# mcu.net
KiCad netlist of a schematic drawn in EAGLE
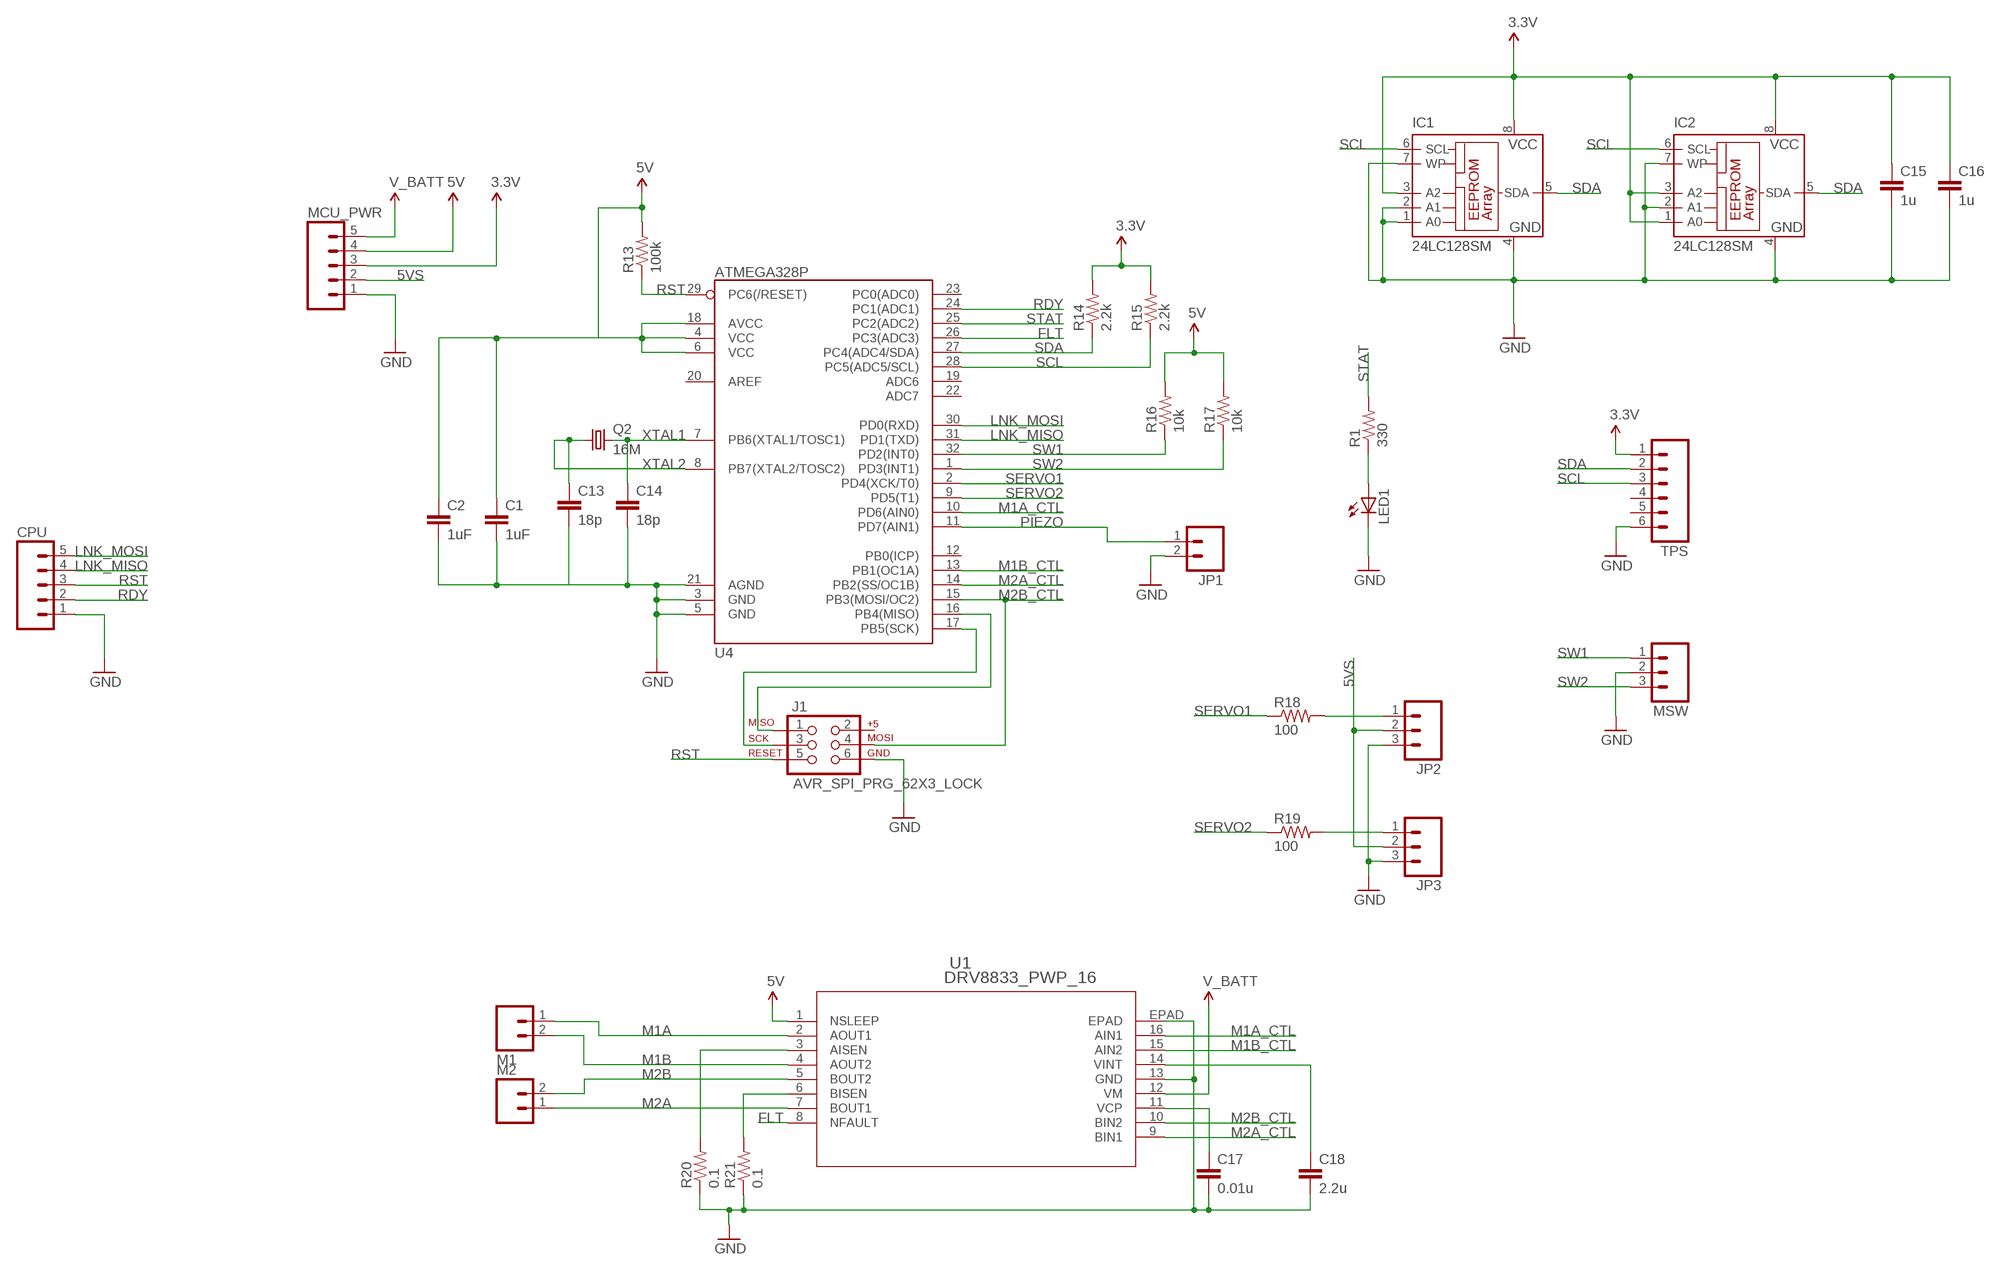
[diagram p0: schematic, sheet 1]

(export (version "E")
  (design (tool "Eeschema 10.0.6"))
  (components
    (comp (ref "C1")
      (value "1uF")
      (footprint "eagle-import:0805")
      (libsource (lib "eagle-import") (part "1UF-25V-10%(0805)"))
    )
    (comp (ref "C2")
      (value "1uF")
      (footprint "eagle-import:0805")
      (libsource (lib "eagle-import") (part "1UF-25V-10%(0805)"))
    )
    (comp (ref "C13")
      (value "18p")
      (footprint "eagle-import:0805")
      (libsource (lib "eagle-import") (part "CAP0805"))
    )
    (comp (ref "C14")
      (value "18p")
      (footprint "eagle-import:0805")
      (libsource (lib "eagle-import") (part "CAP0805"))
    )
    (comp (ref "C15")
      (value "1u")
      (footprint "eagle-import:0805")
      (libsource (lib "eagle-import") (part "CAP0805"))
    )
    (comp (ref "C16")
      (value "1u")
      (footprint "eagle-import:0805")
      (libsource (lib "eagle-import") (part "CAP0805"))
    )
    (comp (ref "C17")
      (value "0.01u")
      (footprint "eagle-import:0805")
      (libsource (lib "eagle-import") (part "CAP0805"))
    )
    (comp (ref "C18")
      (value "2.2u")
      (footprint "eagle-import:0805")
      (libsource (lib "eagle-import") (part "CAP0805"))
    )
    (comp (ref "CPU")
      (value "M05PTH_LONGPADS")
      (footprint "eagle-import:1X05_LONGPADS")
      (libsource (lib "eagle-import") (part "M05PTH_LONGPADS"))
    )
    (comp (ref "IC1")
      (value "24LC128SM")
      (footprint "eagle-import:SO-08M")
      (fields (field (name "MF") "MICROCHIP") (field (name "MPN") "24LC128-I/SM"))
      (libsource (lib "eagle-import") (part "24SMLC128"))
    )
    (comp (ref "IC2")
      (value "24LC128SM")
      (footprint "eagle-import:SO-08M")
      (fields (field (name "MF") "MICROCHIP") (field (name "MPN") "24LC128-I/SM"))
      (libsource (lib "eagle-import") (part "24SMLC128"))
    )
    (comp (ref "J1")
      (value "AVR_SPI_PRG_62X3_LOCK")
      (footprint "eagle-import:2X3_LOCK")
      (libsource (lib "eagle-import") (part "AVR_SPI_PRG_62X3_LOCK"))
    )
    (comp (ref "JP1")
      (value "M02PTH3")
      (footprint "eagle-import:1X02_LONGPADS")
      (libsource (lib "eagle-import") (part "M02PTH3"))
    )
    (comp (ref "JP2")
      (value "M03LOCK_LONGPADS")
      (footprint "eagle-import:1X03_LOCK_LONGPADS")
      (libsource (lib "eagle-import") (part "M03LOCK_LONGPADS"))
    )
    (comp (ref "JP3")
      (value "M03LOCK_LONGPADS")
      (footprint "eagle-import:1X03_LOCK_LONGPADS")
      (libsource (lib "eagle-import") (part "M03LOCK_LONGPADS"))
    )
    (comp (ref "LED1")
      (value "LED1206")
      (footprint "eagle-import:LED-1206")
      (libsource (lib "eagle-import") (part "LED1206"))
    )
    (comp (ref "M1")
      (value "M02PTH3")
      (footprint "eagle-import:1X02_LONGPADS")
      (libsource (lib "eagle-import") (part "M02PTH3"))
    )
    (comp (ref "M2")
      (value "M02PTH3")
      (footprint "eagle-import:1X02_LONGPADS")
      (libsource (lib "eagle-import") (part "M02PTH3"))
    )
    (comp (ref "MCU_PWR")
      (value "M05PTH")
      (footprint "eagle-import:1X05")
      (libsource (lib "eagle-import") (part "M05PTH"))
    )
    (comp (ref "MSW")
      (value "M03LONGPADS")
      (footprint "eagle-import:1X03_LONGPADS")
      (libsource (lib "eagle-import") (part "M03LONGPADS"))
    )
    (comp (ref "Q2")
      (value "16M")
      (footprint "eagle-import:HC49UP")
      (libsource (lib "eagle-import") (part "CRYSTALHC49UP"))
    )
    (comp (ref "R1")
      (value "330")
      (footprint "eagle-import:0805")
      (libsource (lib "eagle-import") (part "RESISTOR0805-RES"))
    )
    (comp (ref "R13")
      (value "100k")
      (footprint "eagle-import:0805")
      (libsource (lib "eagle-import") (part "RESISTOR0805-RES"))
    )
    (comp (ref "R14")
      (value "2.2k")
      (footprint "eagle-import:0805")
      (libsource (lib "eagle-import") (part "RESISTOR0805-RES"))
    )
    (comp (ref "R15")
      (value "2.2k")
      (footprint "eagle-import:0805")
      (libsource (lib "eagle-import") (part "RESISTOR0805-RES"))
    )
    (comp (ref "R16")
      (value "10k")
      (footprint "eagle-import:0805")
      (libsource (lib "eagle-import") (part "RESISTOR0805-RES"))
    )
    (comp (ref "R17")
      (value "10k")
      (footprint "eagle-import:0805")
      (libsource (lib "eagle-import") (part "RESISTOR0805-RES"))
    )
    (comp (ref "R18")
      (value "100")
      (footprint "eagle-import:0805")
      (libsource (lib "eagle-import") (part "RESISTOR0805-RES"))
    )
    (comp (ref "R19")
      (value "100")
      (footprint "eagle-import:0805")
      (libsource (lib "eagle-import") (part "RESISTOR0805-RES"))
    )
    (comp (ref "R20")
      (value "0.1")
      (footprint "eagle-import:1206")
      (libsource (lib "eagle-import") (part "RESISTOR1206"))
    )
    (comp (ref "R21")
      (value "0.1")
      (footprint "eagle-import:1206")
      (libsource (lib "eagle-import") (part "RESISTOR1206"))
    )
    (comp (ref "TPS")
      (value "M06LOCK")
      (footprint "eagle-import:1X06_LOCK")
      (libsource (lib "eagle-import") (part "M06LOCK"))
    )
    (comp (ref "U1")
      (value "DRV8833_PWP_16")
      (footprint "eagle-import:PWP16_2P31X2P46")
      (fields
        (field (name "GENERIC_PART_NUMBER") "DRV8833")
        (field (name "MANUFACTURER") "Texas Instruments")
        (field (name "MANUFACTURER_PART_NUMBER") "drv8833_pwp_16")
      )
      (libsource (lib "eagle-import") (part "DRV8833_PWP_16"))
    )
    (comp (ref "U4")
      (value "ATMEGA328P")
      (footprint "eagle-import:TQFP32-08")
      (libsource (lib "eagle-import") (part "ATMEGA328_SMT"))
    )
  )
  (nets
    (net (code "1") (name "/5VS") (class "Default")
      (node (ref "JP2") (pin "2") (pinfunction "2_2") (pintype "passive"))
      (node (ref "JP3") (pin "2") (pinfunction "2_2") (pintype "passive"))
      (node (ref "MCU_PWR") (pin "2") (pinfunction "2_2") (pintype "passive"))
    )
    (net (code "2") (name "/FLT") (class "Default")
      (node (ref "U1") (pin "8") (pinfunction "NFAULT_8") (pintype "output"))
      (node (ref "U4") (pin "26") (pinfunction "PC3(ADC3)_26") (pintype "bidirectional"))
    )
    (net (code "3") (name "/LNK_MISO") (class "Default")
      (node (ref "CPU") (pin "4") (pinfunction "4_4") (pintype "passive"))
      (node (ref "U4") (pin "31") (pinfunction "PD1(TXD)_31") (pintype "bidirectional"))
    )
    (net (code "4") (name "/LNK_MOSI") (class "Default")
      (node (ref "CPU") (pin "5") (pinfunction "5_5") (pintype "passive"))
      (node (ref "U4") (pin "30") (pinfunction "PD0(RXD)_30") (pintype "bidirectional"))
    )
    (net (code "5") (name "/M1A") (class "Default")
      (node (ref "M1") (pin "1") (pinfunction "1_1") (pintype "passive"))
      (node (ref "U1") (pin "2") (pinfunction "AOUT1_2") (pintype "output"))
    )
    (net (code "6") (name "/M1A_CTL") (class "Default")
      (node (ref "U1") (pin "16") (pinfunction "AIN1_16") (pintype "input"))
      (node (ref "U4") (pin "10") (pinfunction "PD6(AIN0)_10") (pintype "bidirectional"))
    )
    (net (code "7") (name "/M1B") (class "Default")
      (node (ref "M1") (pin "2") (pinfunction "2_2") (pintype "passive"))
      (node (ref "U1") (pin "4") (pinfunction "AOUT2_4") (pintype "output"))
    )
    (net (code "8") (name "/M1B_CTL") (class "Default")
      (node (ref "U1") (pin "15") (pinfunction "AIN2_15") (pintype "input"))
      (node (ref "U4") (pin "13") (pinfunction "PB1(OC1A)_13") (pintype "bidirectional"))
    )
    (net (code "9") (name "/M2A") (class "Default")
      (node (ref "M2") (pin "1") (pinfunction "1_1") (pintype "passive"))
      (node (ref "U1") (pin "7") (pinfunction "BOUT1_7") (pintype "output"))
    )
    (net (code "10") (name "/M2A_CTL") (class "Default")
      (node (ref "U1") (pin "9") (pinfunction "BIN1_9") (pintype "input"))
      (node (ref "U4") (pin "14") (pinfunction "PB2(SS/OC1B)_14") (pintype "bidirectional"))
    )
    (net (code "11") (name "/M2B") (class "Default")
      (node (ref "M2") (pin "2") (pinfunction "2_2") (pintype "passive"))
      (node (ref "U1") (pin "5") (pinfunction "BOUT2_5") (pintype "output"))
    )
    (net (code "12") (name "/M2B_CTL") (class "Default")
      (node (ref "J1") (pin "4") (pinfunction "4_4") (pintype "passive"))
      (node (ref "U1") (pin "10") (pinfunction "BIN2_10") (pintype "input"))
      (node (ref "U4") (pin "15") (pinfunction "PB3(MOSI/OC2)_15") (pintype "bidirectional"))
    )
    (net (code "13") (name "/PIEZO") (class "Default")
      (node (ref "JP1") (pin "1") (pinfunction "1_1") (pintype "passive"))
      (node (ref "U4") (pin "11") (pinfunction "PD7(AIN1)_11") (pintype "bidirectional"))
    )
    (net (code "14") (name "/RDY") (class "Default")
      (node (ref "CPU") (pin "2") (pinfunction "2_2") (pintype "passive"))
      (node (ref "U4") (pin "24") (pinfunction "PC1(ADC1)_24") (pintype "bidirectional"))
    )
    (net (code "15") (name "/RST") (class "Default")
      (node (ref "CPU") (pin "3") (pinfunction "3_3") (pintype "passive"))
      (node (ref "J1") (pin "5") (pinfunction "5_5") (pintype "passive"))
      (node (ref "R13") (pin "1") (pinfunction "1_1") (pintype "passive"))
      (node (ref "U4") (pin "29") (pinfunction "PC6(/RESET)_29") (pintype "bidirectional"))
    )
    (net (code "16") (name "/SCL") (class "Default")
      (node (ref "IC1") (pin "6") (pinfunction "SCL_6") (pintype "input"))
      (node (ref "IC2") (pin "6") (pinfunction "SCL_6") (pintype "input"))
      (node (ref "R15") (pin "1") (pinfunction "1_1") (pintype "passive"))
      (node (ref "TPS") (pin "3") (pinfunction "3_3") (pintype "passive"))
      (node (ref "U4") (pin "28") (pinfunction "PC5(ADC5/SCL)_28") (pintype "bidirectional"))
    )
    (net (code "17") (name "/SDA") (class "Default")
      (node (ref "IC1") (pin "5") (pinfunction "SDA_5") (pintype "bidirectional"))
      (node (ref "IC2") (pin "5") (pinfunction "SDA_5") (pintype "bidirectional"))
      (node (ref "R14") (pin "1") (pinfunction "1_1") (pintype "passive"))
      (node (ref "TPS") (pin "2") (pinfunction "2_2") (pintype "passive"))
      (node (ref "U4") (pin "27") (pinfunction "PC4(ADC4/SDA)_27") (pintype "bidirectional"))
    )
    (net (code "18") (name "/SERVO1") (class "Default")
      (node (ref "R18") (pin "1") (pinfunction "1_1") (pintype "passive"))
      (node (ref "U4") (pin "2") (pinfunction "PD4(XCK/T0)_2") (pintype "bidirectional"))
    )
    (net (code "19") (name "/SERVO2") (class "Default")
      (node (ref "R19") (pin "1") (pinfunction "1_1") (pintype "passive"))
      (node (ref "U4") (pin "9") (pinfunction "PD5(T1)_9") (pintype "bidirectional"))
    )
    (net (code "20") (name "/STAT") (class "Default")
      (node (ref "R1") (pin "2") (pinfunction "2_2") (pintype "passive"))
      (node (ref "U4") (pin "25") (pinfunction "PC2(ADC2)_25") (pintype "bidirectional"))
    )
    (net (code "21") (name "/SW1") (class "Default")
      (node (ref "MSW") (pin "1") (pinfunction "1_1") (pintype "passive"))
      (node (ref "R16") (pin "1") (pinfunction "1_1") (pintype "passive"))
      (node (ref "U4") (pin "32") (pinfunction "PD2(INT0)_32") (pintype "bidirectional"))
    )
    (net (code "22") (name "/SW2") (class "Default")
      (node (ref "MSW") (pin "3") (pinfunction "3_3") (pintype "passive"))
      (node (ref "R17") (pin "1") (pinfunction "1_1") (pintype "passive"))
      (node (ref "U4") (pin "1") (pinfunction "PD3(INT1)_1") (pintype "bidirectional"))
    )
    (net (code "23") (name "/XTAL1") (class "Default")
      (node (ref "C14") (pin "1") (pinfunction "1_1") (pintype "passive"))
      (node (ref "Q2") (pin "2") (pinfunction "2_2") (pintype "passive"))
      (node (ref "U4") (pin "7") (pinfunction "PB6(XTAL1/TOSC1)_7") (pintype "bidirectional"))
    )
    (net (code "24") (name "/XTAL2") (class "Default")
      (node (ref "C13") (pin "1") (pinfunction "1_1") (pintype "passive"))
      (node (ref "Q2") (pin "1") (pinfunction "1_1") (pintype "passive"))
      (node (ref "U4") (pin "8") (pinfunction "PB7(XTAL2/TOSC2)_8") (pintype "bidirectional"))
    )
    (net (code "25") (name "3.3V") (class "Default")
      (node (ref "C15") (pin "1") (pinfunction "1_1") (pintype "passive"))
      (node (ref "C16") (pin "1") (pinfunction "1_1") (pintype "passive"))
      (node (ref "IC1") (pin "3") (pinfunction "A2_3") (pintype "input"))
      (node (ref "IC1") (pin "8") (pinfunction "VCC_8") (pintype "power_in"))
      (node (ref "IC2") (pin "1") (pinfunction "A0_1") (pintype "input"))
      (node (ref "IC2") (pin "3") (pinfunction "A2_3") (pintype "input"))
      (node (ref "IC2") (pin "8") (pinfunction "VCC_8") (pintype "power_in"))
      (node (ref "MCU_PWR") (pin "3") (pinfunction "3_3") (pintype "passive"))
      (node (ref "R14") (pin "2") (pinfunction "2_2") (pintype "passive"))
      (node (ref "R15") (pin "2") (pinfunction "2_2") (pintype "passive"))
      (node (ref "TPS") (pin "1") (pinfunction "1_1") (pintype "passive"))
    )
    (net (code "26") (name "5V") (class "Default")
      (node (ref "C1") (pin "1") (pinfunction "1_1") (pintype "passive"))
      (node (ref "C2") (pin "1") (pinfunction "1_1") (pintype "passive"))
      (node (ref "MCU_PWR") (pin "4") (pinfunction "4_4") (pintype "passive"))
      (node (ref "R13") (pin "2") (pinfunction "2_2") (pintype "passive"))
      (node (ref "R16") (pin "2") (pinfunction "2_2") (pintype "passive"))
      (node (ref "R17") (pin "2") (pinfunction "2_2") (pintype "passive"))
      (node (ref "U1") (pin "1") (pinfunction "NSLEEP_1") (pintype "input"))
      (node (ref "U4") (pin "18") (pinfunction "AVCC_18") (pintype "bidirectional"))
      (node (ref "U4") (pin "4") (pinfunction "VCC_4") (pintype "bidirectional"))
      (node (ref "U4") (pin "6") (pinfunction "VCC_6") (pintype "bidirectional"))
    )
    (net (code "27") (name "GND") (class "Default")
      (node (ref "C1") (pin "2") (pinfunction "2_2") (pintype "passive"))
      (node (ref "C13") (pin "2") (pinfunction "2_2") (pintype "passive"))
      (node (ref "C14") (pin "2") (pinfunction "2_2") (pintype "passive"))
      (node (ref "C15") (pin "2") (pinfunction "2_2") (pintype "passive"))
      (node (ref "C16") (pin "2") (pinfunction "2_2") (pintype "passive"))
      (node (ref "C17") (pin "2") (pinfunction "2_2") (pintype "passive"))
      (node (ref "C18") (pin "2") (pinfunction "2_2") (pintype "passive"))
      (node (ref "C2") (pin "2") (pinfunction "2_2") (pintype "passive"))
      (node (ref "CPU") (pin "1") (pinfunction "1_1") (pintype "passive"))
      (node (ref "IC1") (pin "1") (pinfunction "A0_1") (pintype "input"))
      (node (ref "IC1") (pin "2") (pinfunction "A1_2") (pintype "input"))
      (node (ref "IC1") (pin "4") (pinfunction "GND_4") (pintype "power_in"))
      (node (ref "IC1") (pin "7") (pinfunction "WP_7") (pintype "input"))
      (node (ref "IC2") (pin "2") (pinfunction "A1_2") (pintype "input"))
      (node (ref "IC2") (pin "4") (pinfunction "GND_4") (pintype "power_in"))
      (node (ref "IC2") (pin "7") (pinfunction "WP_7") (pintype "input"))
      (node (ref "J1") (pin "6") (pinfunction "6_6") (pintype "passive"))
      (node (ref "JP1") (pin "2") (pinfunction "2_2") (pintype "passive"))
      (node (ref "JP2") (pin "3") (pinfunction "3_3") (pintype "passive"))
      (node (ref "JP3") (pin "3") (pinfunction "3_3") (pintype "passive"))
      (node (ref "LED1") (pin "C") (pinfunction "C_C") (pintype "passive"))
      (node (ref "MCU_PWR") (pin "1") (pinfunction "1_1") (pintype "passive"))
      (node (ref "MSW") (pin "2") (pinfunction "2_2") (pintype "passive"))
      (node (ref "R20") (pin "1") (pinfunction "1_1") (pintype "passive"))
      (node (ref "R21") (pin "1") (pinfunction "1_1") (pintype "passive"))
      (node (ref "TPS") (pin "6") (pinfunction "6_6") (pintype "passive"))
      (node (ref "U1") (pin "13") (pinfunction "GND_13") (pintype "power_in"))
      (node (ref "U1") (pin "EPAD") (pinfunction "EPAD_EPAD") (pintype "passive"))
      (node (ref "U4") (pin "21") (pinfunction "AGND_21") (pintype "bidirectional"))
      (node (ref "U4") (pin "3") (pinfunction "GND_3") (pintype "bidirectional"))
      (node (ref "U4") (pin "5") (pinfunction "GND_5") (pintype "bidirectional"))
    )
    (net (code "28") (name "Net-(JP2-Pad1)") (class "Default")
      (node (ref "JP2") (pin "1") (pinfunction "1_1") (pintype "passive"))
      (node (ref "R18") (pin "2") (pinfunction "2_2") (pintype "passive"))
    )
    (net (code "29") (name "Net-(JP3-Pad1)") (class "Default")
      (node (ref "JP3") (pin "1") (pinfunction "1_1") (pintype "passive"))
      (node (ref "R19") (pin "2") (pinfunction "2_2") (pintype "passive"))
    )
    (net (code "30") (name "Net-(LED1-PadA)") (class "Default")
      (node (ref "LED1") (pin "A") (pinfunction "A_A") (pintype "passive"))
      (node (ref "R1") (pin "1") (pinfunction "1_1") (pintype "passive"))
    )
    (net (code "31") (name "Net-(U1-AISEN)") (class "Default")
      (node (ref "R20") (pin "2") (pinfunction "2_2") (pintype "passive"))
      (node (ref "U1") (pin "3") (pinfunction "AISEN_3") (pintype "bidirectional"))
    )
    (net (code "32") (name "Net-(U1-BISEN)") (class "Default")
      (node (ref "R21") (pin "2") (pinfunction "2_2") (pintype "passive"))
      (node (ref "U1") (pin "6") (pinfunction "BISEN_6") (pintype "bidirectional"))
    )
    (net (code "33") (name "Net-(U1-VCP)") (class "Default")
      (node (ref "C17") (pin "1") (pinfunction "1_1") (pintype "passive"))
      (node (ref "U1") (pin "11") (pinfunction "VCP_11") (pintype "bidirectional"))
    )
    (net (code "34") (name "Net-(U1-VINT)") (class "Default")
      (node (ref "C18") (pin "1") (pinfunction "1_1") (pintype "passive"))
      (node (ref "U1") (pin "14") (pinfunction "VINT_14") (pintype "power_in"))
    )
    (net (code "35") (name "Net-(U4-PB4(MISO))") (class "Default")
      (node (ref "J1") (pin "1") (pinfunction "1_1") (pintype "passive"))
      (node (ref "U4") (pin "16") (pinfunction "PB4(MISO)_16") (pintype "bidirectional"))
    )
    (net (code "36") (name "Net-(U4-PB5(SCK))") (class "Default")
      (node (ref "J1") (pin "3") (pinfunction "3_3") (pintype "passive"))
      (node (ref "U4") (pin "17") (pinfunction "PB5(SCK)_17") (pintype "bidirectional"))
    )
    (net (code "37") (name "V_BATT") (class "Default")
      (node (ref "MCU_PWR") (pin "5") (pinfunction "5_5") (pintype "passive"))
      (node (ref "U1") (pin "12") (pinfunction "VM_12") (pintype "power_in"))
    )
    (net (code "38") (name "unconnected-(J1-Pad2)") (class "Default")
      (node (ref "J1") (pin "2") (pinfunction "2_2") (pintype "passive"))
    )
    (net (code "39") (name "unconnected-(TPS-Pad4)") (class "Default")
      (node (ref "TPS") (pin "4") (pinfunction "4_4") (pintype "passive"))
    )
    (net (code "40") (name "unconnected-(TPS-Pad5)") (class "Default")
      (node (ref "TPS") (pin "5") (pinfunction "5_5") (pintype "passive"))
    )
    (net (code "41") (name "unconnected-(U4-ADC6-Pad19)") (class "Default")
      (node (ref "U4") (pin "19") (pinfunction "ADC6_19") (pintype "bidirectional"))
    )
    (net (code "42") (name "unconnected-(U4-ADC7-Pad22)") (class "Default")
      (node (ref "U4") (pin "22") (pinfunction "ADC7_22") (pintype "bidirectional"))
    )
    (net (code "43") (name "unconnected-(U4-AREF-Pad20)") (class "Default")
      (node (ref "U4") (pin "20") (pinfunction "AREF_20") (pintype "bidirectional"))
    )
    (net (code "44") (name "unconnected-(U4-PB0(ICP)-Pad12)") (class "Default")
      (node (ref "U4") (pin "12") (pinfunction "PB0(ICP)_12") (pintype "bidirectional"))
    )
    (net (code "45") (name "unconnected-(U4-PC0(ADC0)-Pad23)") (class "Default")
      (node (ref "U4") (pin "23") (pinfunction "PC0(ADC0)_23") (pintype "bidirectional"))
    )
  )
)
